# Ultrasound.net
KiCad netlist of a schematic drawn in Altium Designer
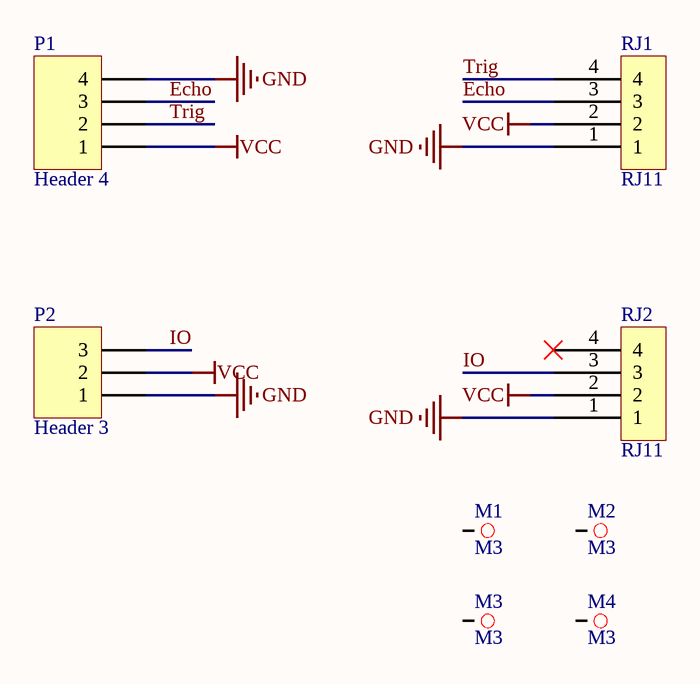
[diagram p0: Ultrasound.SchDoc]

(export (version "E")
  (design (tool "Eeschema 10.0.6"))
  (components
    (comp (ref "M1") (value "M3") (footprint "M3") (libsource (lib "QQW-1.SCHLIB") (part "M3")))
    (comp (ref "M2") (value "M3") (footprint "M3") (libsource (lib "QQW-1.SCHLIB") (part "M3")))
    (comp (ref "M3") (value "M3") (footprint "M3") (libsource (lib "QQW-1.SCHLIB") (part "M3")))
    (comp (ref "M4") (value "M3") (footprint "M3") (libsource (lib "QQW-1.SCHLIB") (part "M3")))
    (comp (ref "P1")
      (value "Header 4")
      (footprint "HDR1X4")
      (description "Header, 4-Pin")
      (fields (field (name "PUBLISHER") "Altium Limited"))
      (libsource (lib "Miscellaneous Connectors") (part "Header 4"))
    )
    (comp (ref "P2")
      (value "Header 3")
      (footprint "HDR1X3")
      (description "Header, 3-Pin")
      (fields (field (name "PUBLISHER") "Altium Limited"))
      (libsource (lib "Miscellaneous Connectors") (part "Header 3"))
    )
    (comp (ref "RJ1") (value "RJ11") (footprint "RJ11") (libsource (lib "少儿智能车") (part "RJ11")))
    (comp (ref "RJ2") (value "RJ11") (footprint "RJ11") (libsource (lib "少儿智能车") (part "RJ11")))
  )
  (nets
    (net (code "1") (name "/Echo") (class "Default")
      (node (ref "P1") (pin "3") (pinfunction "3_3") (pintype "passive"))
      (node (ref "RJ1") (pin "3") (pinfunction "3_3") (pintype "passive"))
    )
    (net (code "2") (name "/IO") (class "Default")
      (node (ref "P2") (pin "3") (pinfunction "3_3") (pintype "passive"))
      (node (ref "RJ2") (pin "3") (pinfunction "3_3") (pintype "passive"))
    )
    (net (code "3") (name "/Trig") (class "Default")
      (node (ref "P1") (pin "2") (pinfunction "2_2") (pintype "passive"))
      (node (ref "RJ1") (pin "4") (pinfunction "4_4") (pintype "passive"))
    )
    (net (code "4") (name "GND") (class "Default")
      (node (ref "P1") (pin "4") (pinfunction "4_4") (pintype "passive"))
      (node (ref "P2") (pin "1") (pinfunction "1_1") (pintype "passive"))
      (node (ref "RJ1") (pin "1") (pinfunction "1_1") (pintype "passive"))
      (node (ref "RJ2") (pin "1") (pinfunction "1_1") (pintype "passive"))
    )
    (net (code "5") (name "VCC") (class "Default")
      (node (ref "P1") (pin "1") (pinfunction "1_1") (pintype "passive"))
      (node (ref "P2") (pin "2") (pinfunction "2_2") (pintype "passive"))
      (node (ref "RJ1") (pin "2") (pinfunction "2_2") (pintype "passive"))
      (node (ref "RJ2") (pin "2") (pinfunction "2_2") (pintype "passive"))
    )
    (net (code "6") (name "unconnected-(M1-Pad0)") (class "Default")
      (node (ref "M1") (pin "0") (pinfunction "0_0") (pintype "passive"))
    )
    (net (code "7") (name "unconnected-(M2-Pad0)") (class "Default")
      (node (ref "M2") (pin "0") (pinfunction "0_0") (pintype "passive"))
    )
    (net (code "8") (name "unconnected-(M3-Pad0)") (class "Default")
      (node (ref "M3") (pin "0") (pinfunction "0_0") (pintype "passive"))
    )
    (net (code "9") (name "unconnected-(M4-Pad0)") (class "Default")
      (node (ref "M4") (pin "0") (pinfunction "0_0") (pintype "passive"))
    )
    (net (code "10") (name "unconnected-(RJ2-Pad4)") (class "Default")
      (node (ref "RJ2") (pin "4") (pinfunction "4_4") (pintype "passive+no_connect"))
    )
  )
)
